# InkTime.net
KiCad netlist of a schematic drawn in EAGLE
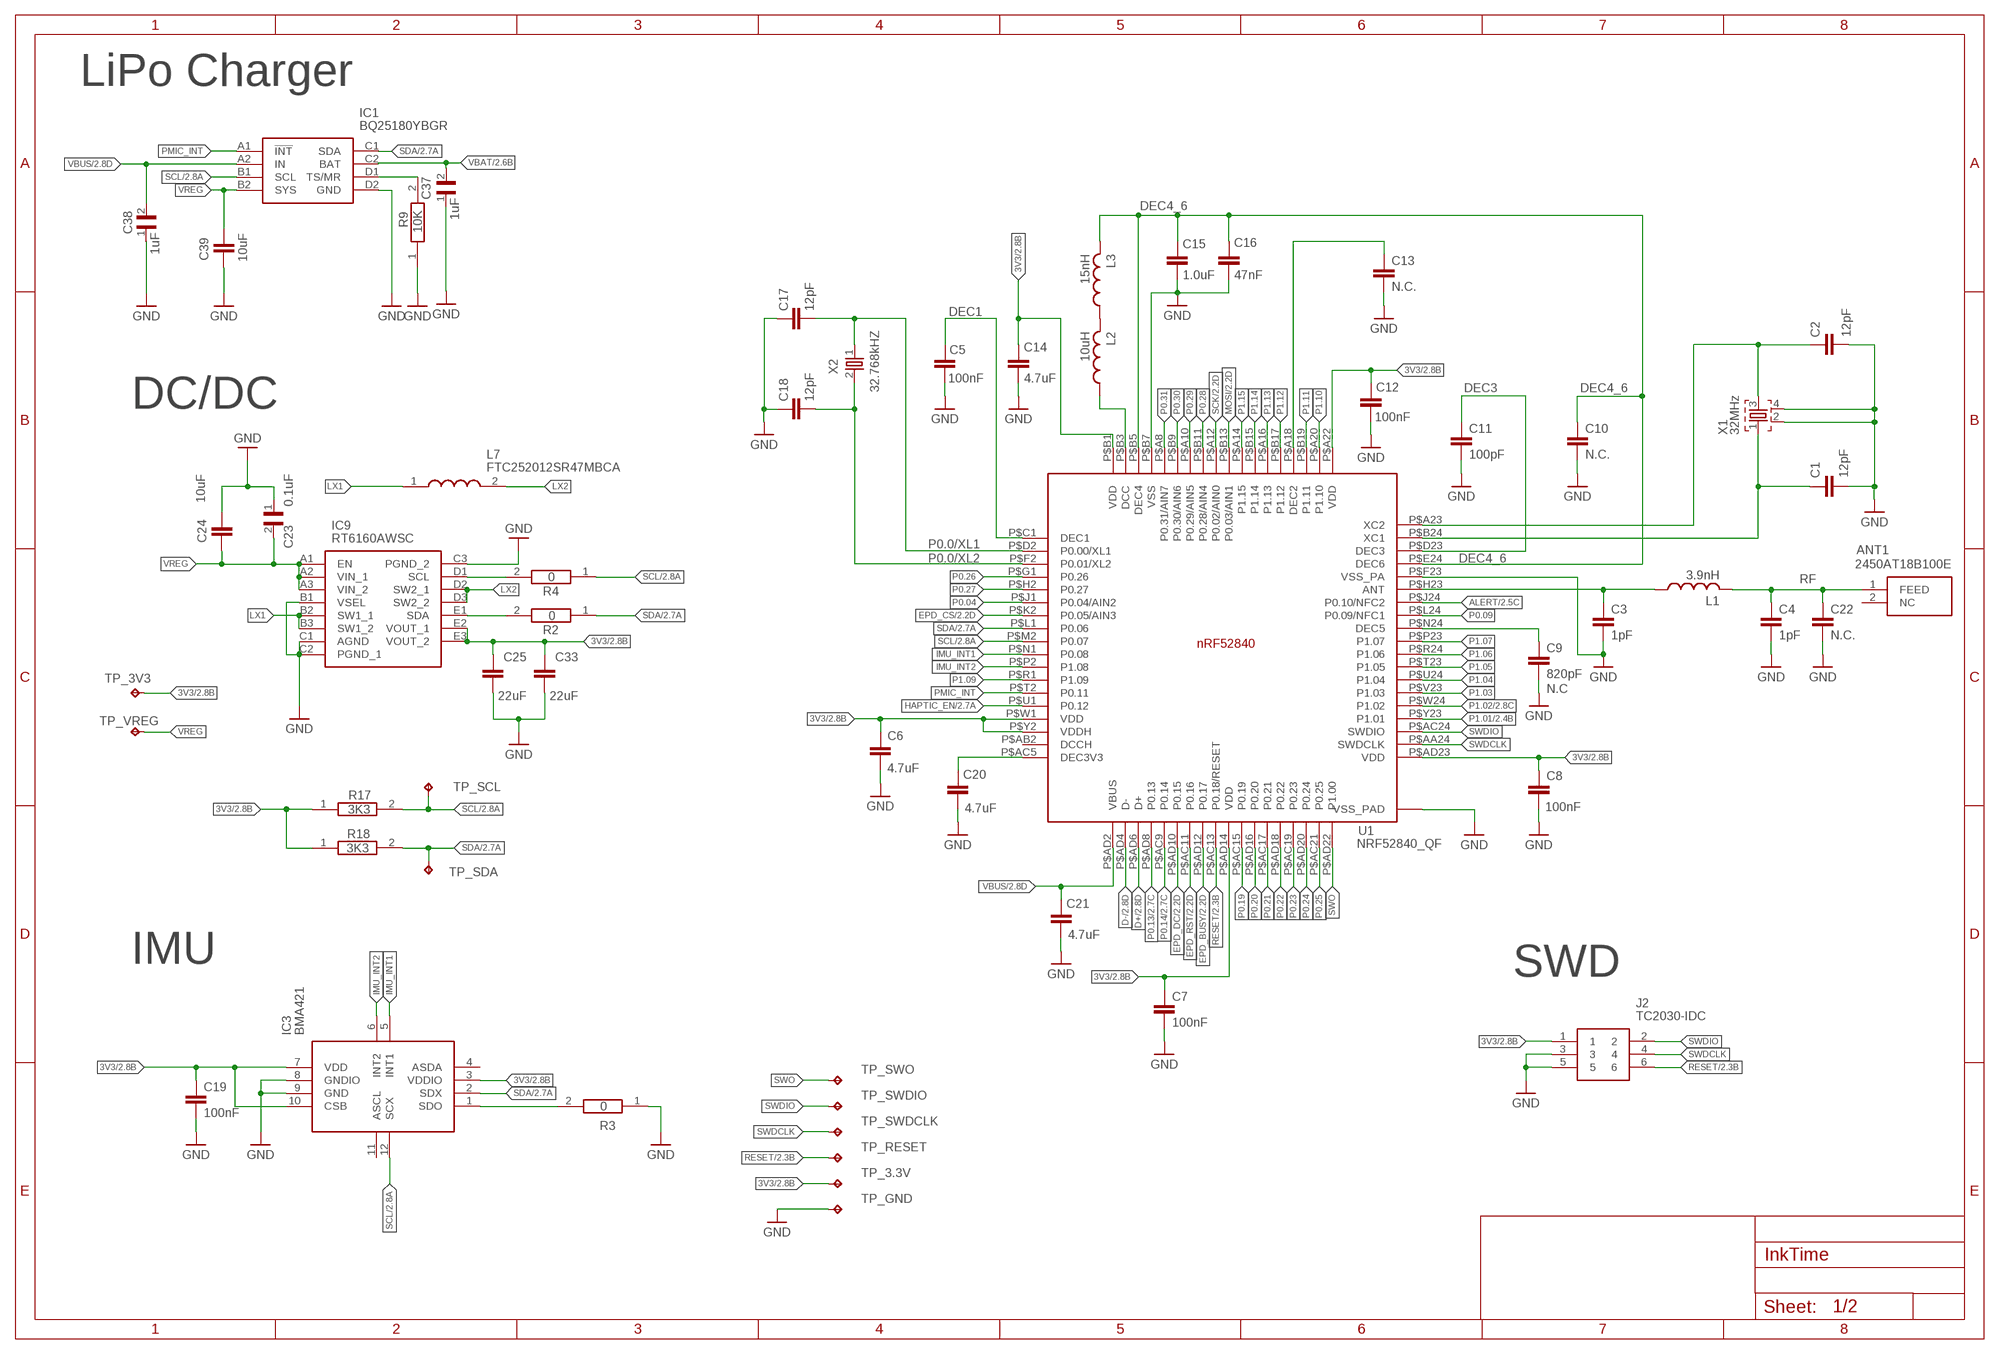
[diagram p0: schematic, sheet 1]
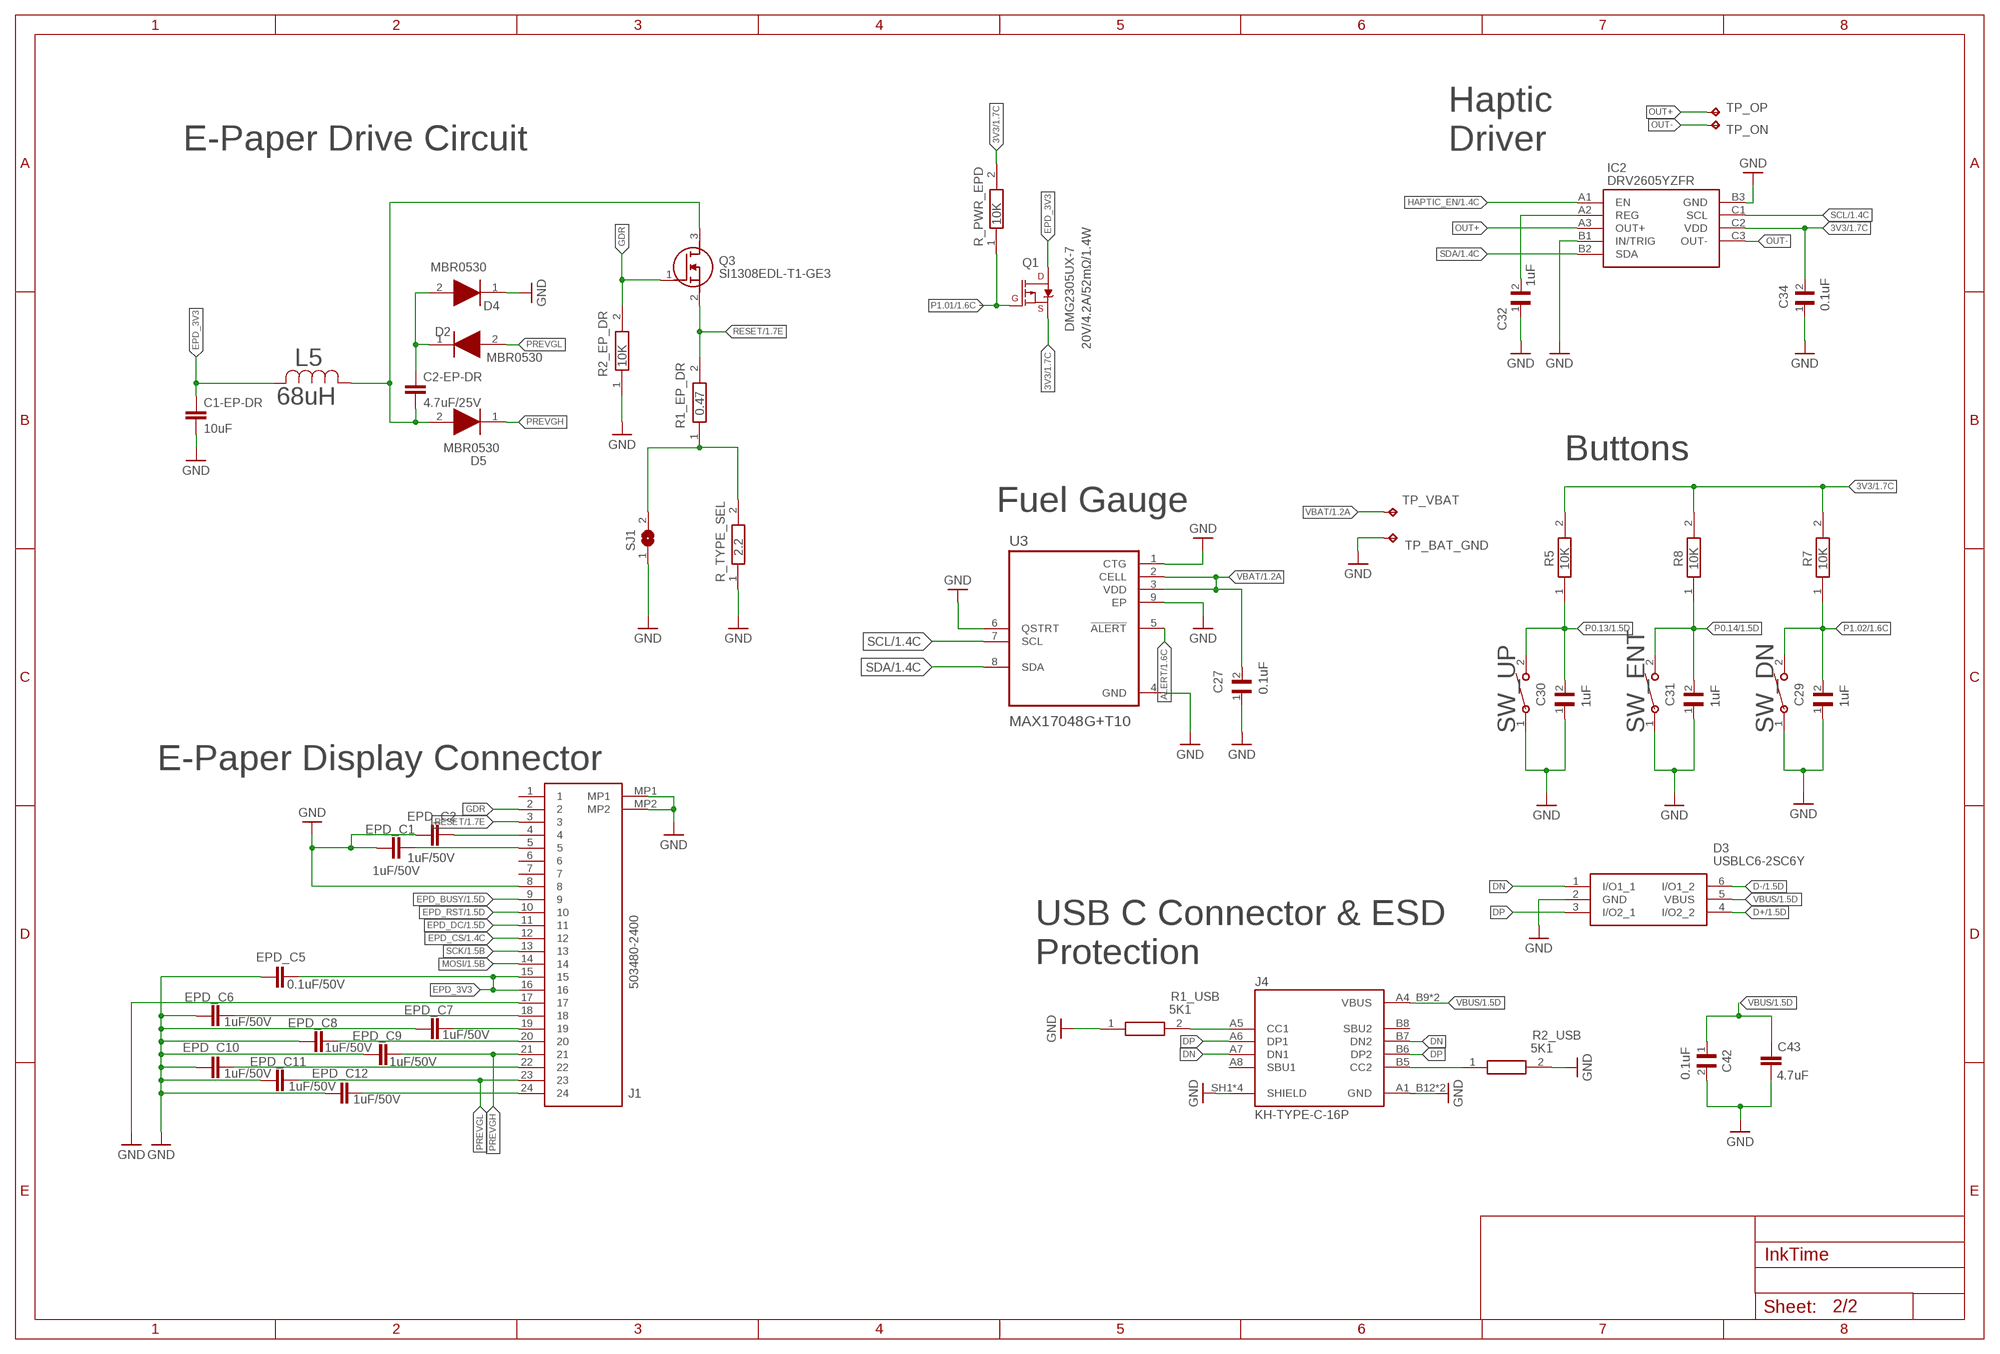
[diagram p1: schematic, sheet 2]

(export (version "E")
  (design (tool "Eeschema 10.0.6"))
  (components
    (comp (ref "ANT1")
      (value "2450AT18B100E")
      (footprint "eagle-import:2450AT18B100E_ANTC3216X140N")
      (fields (field (name "MOUSER_PART_NUMBER") "609-2450AT18B100E"))
      (libsource (lib "eagle-import") (part "2450AT18B100E_2450AT18B100E"))
    )
    (comp (ref "C1")
      (value "12pF")
      (footprint "eagle-import:NORDIC_NRF_3_RESC0201_L")
      (libsource (lib "eagle-import") (part "NORDIC_NRF_3_CAPACITOR_0201_L"))
    )
    (comp (ref "C2")
      (value "12pF")
      (footprint "eagle-import:NORDIC_NRF_3_RESC0201_L")
      (libsource (lib "eagle-import") (part "NORDIC_NRF_3_CAPACITOR_0201_L"))
    )
    (comp (ref "C3")
      (value "1pF")
      (footprint "eagle-import:NORDIC_NRF_3_RESC0201_L")
      (libsource (lib "eagle-import") (part "NORDIC_NRF_3_CAPACITOR_0201_L"))
    )
    (comp (ref "C4")
      (value "1pF")
      (footprint "eagle-import:NORDIC_NRF_3_RESC0201_L")
      (libsource (lib "eagle-import") (part "NORDIC_NRF_3_CAPACITOR_0201_L"))
    )
    (comp (ref "C5")
      (value "100nF")
      (footprint "eagle-import:PERFECT_0402_0402")
      (libsource (lib "eagle-import") (part "PERFECT_0402_CAP_0402"))
    )
    (comp (ref "C6")
      (value "4.7uF")
      (footprint "eagle-import:PERFECT_0402_0402")
      (libsource (lib "eagle-import") (part "PERFECT_0402_CAP_0402"))
    )
    (comp (ref "C7")
      (value "100nF")
      (footprint "eagle-import:NORDIC_NRF_3_RESC0201_L")
      (libsource (lib "eagle-import") (part "NORDIC_NRF_3_CAPACITOR_0201_L"))
    )
    (comp (ref "C8")
      (value "100nF")
      (footprint "eagle-import:NORDIC_NRF_3_RESC0201_L")
      (libsource (lib "eagle-import") (part "NORDIC_NRF_3_CAPACITOR_0201_L"))
    )
    (comp (ref "C9")
      (value "820pF")
      (footprint "eagle-import:NORDIC_NRF_3_RESC0201_L")
      (libsource (lib "eagle-import") (part "NORDIC_NRF_3_CAPACITOR_0201_L"))
    )
    (comp (ref "C10")
      (value "N.C.")
      (footprint "eagle-import:NORDIC_NRF_3_RESC0201_L")
      (libsource (lib "eagle-import") (part "NORDIC_NRF_3_CAPACITOR_0201_L"))
    )
    (comp (ref "C11")
      (value "100pF")
      (footprint "eagle-import:NORDIC_NRF_3_RESC0201_L")
      (libsource (lib "eagle-import") (part "NORDIC_NRF_3_CAPACITOR_0201_L"))
    )
    (comp (ref "C12")
      (value "100nF")
      (footprint "eagle-import:NORDIC_NRF_3_RESC0201_L")
      (libsource (lib "eagle-import") (part "NORDIC_NRF_3_CAPACITOR_0201_L"))
    )
    (comp (ref "C13")
      (value "N.C.")
      (footprint "eagle-import:NORDIC_NRF_3_RESC0201_L")
      (libsource (lib "eagle-import") (part "NORDIC_NRF_3_CAPACITOR_0201_L"))
    )
    (comp (ref "C14")
      (value "4.7uF")
      (footprint "eagle-import:PERFECT_0402_0402")
      (libsource (lib "eagle-import") (part "PERFECT_0402_CAP_0402"))
    )
    (comp (ref "C15")
      (value "1.0uF")
      (footprint "eagle-import:PERFECT_0402_0402")
      (libsource (lib "eagle-import") (part "PERFECT_0402_CAP_0402"))
    )
    (comp (ref "C16")
      (value "47nF")
      (footprint "eagle-import:NORDIC_NRF_3_RESC0201_L")
      (libsource (lib "eagle-import") (part "NORDIC_NRF_3_CAPACITOR_0201_L"))
    )
    (comp (ref "C17")
      (value "12pF")
      (footprint "eagle-import:NORDIC_NRF_3_RESC0201_L")
      (libsource (lib "eagle-import") (part "NORDIC_NRF_3_CAPACITOR_0201_L"))
    )
    (comp (ref "C18")
      (value "12pF")
      (footprint "eagle-import:NORDIC_NRF_3_RESC0201_L")
      (libsource (lib "eagle-import") (part "NORDIC_NRF_3_CAPACITOR_0201_L"))
    )
    (comp (ref "C19")
      (value "100nF")
      (footprint "eagle-import:NORDIC_NRF_3_RESC0201_L")
      (libsource (lib "eagle-import") (part "NORDIC_NRF_3_CAPACITOR_0201_L"))
    )
    (comp (ref "C20")
      (value "4.7uF")
      (footprint "eagle-import:PERFECT_0402_0402")
      (libsource (lib "eagle-import") (part "PERFECT_0402_CAP_0402"))
    )
    (comp (ref "C21")
      (value "4.7uF")
      (footprint "eagle-import:PERFECT_0402_0402")
      (libsource (lib "eagle-import") (part "PERFECT_0402_CAP_0402"))
    )
    (comp (ref "C22")
      (value "N.C.")
      (footprint "eagle-import:NORDIC_NRF_3_RESC0201_L")
      (libsource (lib "eagle-import") (part "NORDIC_NRF_3_CAPACITOR_0201_L"))
    )
    (comp (ref "C23")
      (value "0.1uF")
      (footprint "eagle-import:GRM011R60J152KE01L_1_0201")
      (libsource (lib "eagle-import") (part "GRM011R60J152KE01L_1_GRM011R60J152KE01L"))
    )
    (comp (ref "C24")
      (value "10uF")
      (footprint "eagle-import:PERFECT_0402_0402")
      (libsource (lib "eagle-import") (part "PERFECT_0402_CAP_0402"))
    )
    (comp (ref "C25")
      (value "22uF")
      (footprint "eagle-import:PERFECT_0402_0402")
      (libsource (lib "eagle-import") (part "PERFECT_0402_CAP_0402"))
    )
    (comp (ref "C33")
      (value "22uF")
      (footprint "eagle-import:PERFECT_0402_0402")
      (libsource (lib "eagle-import") (part "PERFECT_0402_CAP_0402"))
    )
    (comp (ref "C37")
      (value "1uF")
      (footprint "eagle-import:GRM011R60J152KE01L_1_0201")
      (libsource (lib "eagle-import") (part "GRM011R60J152KE01L_1_GRM011R60J152KE01L"))
    )
    (comp (ref "C38")
      (value "1uF")
      (footprint "eagle-import:GRM011R60J152KE01L_1_0201")
      (libsource (lib "eagle-import") (part "GRM011R60J152KE01L_1_GRM011R60J152KE01L"))
    )
    (comp (ref "C39")
      (value "10uF")
      (footprint "eagle-import:PERFECT_0402_0402")
      (libsource (lib "eagle-import") (part "PERFECT_0402_CAP_0402"))
    )
    (comp (ref "IC1")
      (value "BQ25180YBGR")
      (footprint "eagle-import:BQ25180YBGR_BGA8C40P2X4_100X155X50")
      (fields (field (name "MOUSER_PART_NUMBER") "595-BQ25180YBGR"))
      (libsource (lib "eagle-import") (part "BQ25180YBGR_BQ25180YBGR"))
    )
    (comp (ref "IC3")
      (value "BMA421")
      (footprint "eagle-import:BMA423_BMA423")
      (fields (field (name "ARROW_PART_NUMBER") "BMA423") (field (name "MOUSER_PART_NUMBER") "262-BMA423"))
      (libsource (lib "eagle-import") (part "BMA423_BMA423"))
    )
    (comp (ref "IC9")
      (value "RT6160AWSC")
      (footprint "eagle-import:RT6160AWSC_BGA15C40P3X5_140X230X60")
      (fields (field (name "MOUSER_PART_NUMBER") "835-RT6160AWSC"))
      (libsource (lib "eagle-import") (part "RT6160AWSC_RT6160AWSC"))
    )
    (comp (ref "J2")
      (value "TC2030-IDC")
      (footprint "eagle-import:TC2030-IDC_TC2030IDC")
      (libsource (lib "eagle-import") (part "TC2030-IDC_TC2030-IDC"))
    )
    (comp (ref "L1")
      (value "3.9nH")
      (footprint "eagle-import:NORDIC_NRF_2_RESC0402_L")
      (libsource (lib "eagle-import") (part "NORDIC_NRF_2_INDUCTOR_0402_L"))
    )
    (comp (ref "L2")
      (value "10uH")
      (footprint "eagle-import:NORDIC_NRF_2_RESC0402_L")
      (libsource (lib "eagle-import") (part "NORDIC_NRF_2_INDUCTOR_0402_L"))
    )
    (comp (ref "L3")
      (value "15nH")
      (footprint "eagle-import:NORDIC_NRF_2_RESC0402_L")
      (libsource (lib "eagle-import") (part "NORDIC_NRF_2_INDUCTOR_0402_L"))
    )
    (comp (ref "L7")
      (value "FTC252012SR47MBCA")
      (footprint "eagle-import:MLP2016SR47MT0S1_INDC2016X100N")
      (libsource (lib "eagle-import") (part "MLP2016SR47MT0S1_FTC252012SR47MBCA"))
    )
    (comp (ref "R2")
      (value "0")
      (footprint "eagle-import:ERA-1AEB3401C_0201")
      (libsource (lib "eagle-import") (part "ERA-1AEB3401C_CPF0201D7K68C1"))
    )
    (comp (ref "R3")
      (value "0")
      (footprint "eagle-import:ERA-1AEB3401C_0201")
      (libsource (lib "eagle-import") (part "ERA-1AEB3401C_CPF0201D7K68C1"))
    )
    (comp (ref "R4")
      (value "0")
      (footprint "eagle-import:ERA-1AEB3401C_0201")
      (libsource (lib "eagle-import") (part "ERA-1AEB3401C_CPF0201D7K68C1"))
    )
    (comp (ref "R9")
      (value "10K")
      (footprint "eagle-import:ERA-1AEB3401C_0201")
      (libsource (lib "eagle-import") (part "ERA-1AEB3401C_CPF0201D7K68C1"))
    )
    (comp (ref "R17")
      (value "3K3")
      (footprint "eagle-import:ERA-1AEB3401C_0201")
      (libsource (lib "eagle-import") (part "ERA-1AEB3401C_CPF0201D7K68C1"))
    )
    (comp (ref "R18")
      (value "3K3")
      (footprint "eagle-import:ERA-1AEB3401C_0201")
      (libsource (lib "eagle-import") (part "ERA-1AEB3401C_CPF0201D7K68C1"))
    )
    (comp (ref "TP_3.3V")
      (value "HECTOR_WATCH_1_TPTP20R")
      (footprint "eagle-import:HECTOR_WATCH_1_TP20R")
      (libsource (lib "eagle-import") (part "HECTOR_WATCH_1_TPTP20R"))
    )
    (comp (ref "TP_3V3")
      (value "HECTOR_WATCH_1_TPTP20R")
      (footprint "eagle-import:HECTOR_WATCH_1_TP20R")
      (libsource (lib "eagle-import") (part "HECTOR_WATCH_1_TPTP20R"))
    )
    (comp (ref "TP_GND")
      (value "HECTOR_WATCH_1_TPTP20R")
      (footprint "eagle-import:HECTOR_WATCH_1_TP20R")
      (libsource (lib "eagle-import") (part "HECTOR_WATCH_1_TPTP20R"))
    )
    (comp (ref "TP_RESET")
      (value "HECTOR_WATCH_1_TPTP20R")
      (footprint "eagle-import:HECTOR_WATCH_1_TP20R")
      (libsource (lib "eagle-import") (part "HECTOR_WATCH_1_TPTP20R"))
    )
    (comp (ref "TP_SCL")
      (value "HECTOR_WATCH_1_TPTP20R")
      (footprint "eagle-import:HECTOR_WATCH_1_TP20R")
      (libsource (lib "eagle-import") (part "HECTOR_WATCH_1_TPTP20R"))
    )
    (comp (ref "TP_SDA")
      (value "HECTOR_WATCH_1_TPTP20R")
      (footprint "eagle-import:HECTOR_WATCH_1_TP20R")
      (libsource (lib "eagle-import") (part "HECTOR_WATCH_1_TPTP20R"))
    )
    (comp (ref "TP_SWDCLK")
      (value "HECTOR_WATCH_1_TPTP20R")
      (footprint "eagle-import:HECTOR_WATCH_1_TP20R")
      (libsource (lib "eagle-import") (part "HECTOR_WATCH_1_TPTP20R"))
    )
    (comp (ref "TP_SWDIO")
      (value "HECTOR_WATCH_1_TPTP20R")
      (footprint "eagle-import:HECTOR_WATCH_1_TP20R")
      (libsource (lib "eagle-import") (part "HECTOR_WATCH_1_TPTP20R"))
    )
    (comp (ref "TP_SWO")
      (value "HECTOR_WATCH_1_TPTP20R")
      (footprint "eagle-import:HECTOR_WATCH_1_TP20R")
      (libsource (lib "eagle-import") (part "HECTOR_WATCH_1_TPTP20R"))
    )
    (comp (ref "TP_VREG")
      (value "HECTOR_WATCH_1_TPTP20R")
      (footprint "eagle-import:HECTOR_WATCH_1_TP20R")
      (libsource (lib "eagle-import") (part "HECTOR_WATCH_1_TPTP20R"))
    )
    (comp (ref "U1")
      (value "NRF52840_QF")
      (footprint "eagle-import:NORDIC_NRF_4_AQFN50P700X700X85_HS-74N")
      (libsource (lib "eagle-import") (part "NORDIC_NRF_4_NRF52840_QF"))
    )
    (comp (ref "X1")
      (value "32MHz")
      (footprint "eagle-import:NORDIC_NRF_BT-XTAL_2016_N")
      (libsource (lib "eagle-import") (part "NORDIC_NRF_XTAL_32MHZ"))
    )
    (comp (ref "X2")
      (value "32.768kHZ")
      (footprint "eagle-import:NORDIC_NRF_1_XTAL_3215_N")
      (libsource (lib "eagle-import") (part "NORDIC_NRF_1_XTAL_32KHZ"))
    )
    (comp (ref "C1-EP-DR")
      (value "10uF")
      (footprint "eagle-import:PERFECT_0402_0402")
      (libsource (lib "eagle-import") (part "PERFECT_0402_CAP_0402"))
    )
    (comp (ref "C2-EP-DR")
      (value "4.7uF/25V")
      (footprint "eagle-import:PERFECT_0402_0402")
      (libsource (lib "eagle-import") (part "PERFECT_0402_CAP_0402"))
    )
    (comp (ref "C27")
      (value "0.1uF")
      (footprint "eagle-import:GRM011R60J152KE01L_1_0201")
      (libsource (lib "eagle-import") (part "GRM011R60J152KE01L_1_GRM011R60J152KE01L"))
    )
    (comp (ref "C29")
      (value "1uF")
      (footprint "eagle-import:GRM011R60J152KE01L_1_0201")
      (libsource (lib "eagle-import") (part "GRM011R60J152KE01L_1_GRM011R60J152KE01L"))
    )
    (comp (ref "C30")
      (value "1uF")
      (footprint "eagle-import:GRM011R60J152KE01L_1_0201")
      (libsource (lib "eagle-import") (part "GRM011R60J152KE01L_1_GRM011R60J152KE01L"))
    )
    (comp (ref "C31")
      (value "1uF")
      (footprint "eagle-import:GRM011R60J152KE01L_1_0201")
      (libsource (lib "eagle-import") (part "GRM011R60J152KE01L_1_GRM011R60J152KE01L"))
    )
    (comp (ref "C32")
      (value "1uF")
      (footprint "eagle-import:GRM011R60J152KE01L_1_0201")
      (libsource (lib "eagle-import") (part "GRM011R60J152KE01L_1_GRM011R60J152KE01L"))
    )
    (comp (ref "C34")
      (value "0.1uF")
      (footprint "eagle-import:GRM011R60J152KE01L_1_0201")
      (libsource (lib "eagle-import") (part "GRM011R60J152KE01L_1_GRM011R60J152KE01L"))
    )
    (comp (ref "C42")
      (value "0.1uF")
      (footprint "eagle-import:GRM011R60J152KE01L_1_0201")
      (libsource (lib "eagle-import") (part "GRM011R60J152KE01L_1_GRM011R60J152KE01L"))
    )
    (comp (ref "C43")
      (value "4.7uF")
      (footprint "eagle-import:PERFECT_0402_0402")
      (libsource (lib "eagle-import") (part "PERFECT_0402_CAP_0402"))
    )
    (comp (ref "D2")
      (value "MBR0530")
      (footprint "eagle-import:ESP32_C6_LIBRARY_5_SOD3716X135N")
      (fields (field (name "MF") "ON Semiconductor"))
      (libsource (lib "eagle-import") (part "ESP32_C6_LIBRARY_5_MBR0530"))
    )
    (comp (ref "D3")
      (value "USBLC6-2SC6Y")
      (footprint "eagle-import:ESP32_C6_LIBRARY_3_SOT95P280X145-6N")
      (fields (field (name "MF") "STMicroelectronics"))
      (libsource (lib "eagle-import") (part "ESP32_C6_LIBRARY_3_USBLC6-2SC6Y"))
    )
    (comp (ref "D4")
      (value "MBR0530")
      (footprint "eagle-import:ESP32_C6_LIBRARY_5_SOD3716X135N")
      (fields (field (name "MF") "ON Semiconductor"))
      (libsource (lib "eagle-import") (part "ESP32_C6_LIBRARY_5_MBR0530"))
    )
    (comp (ref "D5")
      (value "MBR0530")
      (footprint "eagle-import:ESP32_C6_LIBRARY_5_SOD3716X135N")
      (fields (field (name "MF") "ON Semiconductor"))
      (libsource (lib "eagle-import") (part "ESP32_C6_LIBRARY_5_MBR0530"))
    )
    (comp (ref "EPD_C1")
      (value "1uF/50V")
      (footprint "eagle-import:PERFECT_0402_0402")
      (libsource (lib "eagle-import") (part "PERFECT_0402_CAP_0402"))
    )
    (comp (ref "EPD_C2")
      (value "1uF/50V")
      (footprint "eagle-import:PERFECT_0402_0402")
      (libsource (lib "eagle-import") (part "PERFECT_0402_CAP_0402"))
    )
    (comp (ref "EPD_C5")
      (value "0.1uF/50V")
      (footprint "eagle-import:NORDIC_NRF_3_RESC0201_L")
      (libsource (lib "eagle-import") (part "NORDIC_NRF_3_CAPACITOR_0201_L"))
    )
    (comp (ref "EPD_C6")
      (value "1uF/50V")
      (footprint "eagle-import:PERFECT_0402_0402")
      (libsource (lib "eagle-import") (part "PERFECT_0402_CAP_0402"))
    )
    (comp (ref "EPD_C7")
      (value "1uF/50V")
      (footprint "eagle-import:PERFECT_0402_0402")
      (libsource (lib "eagle-import") (part "PERFECT_0402_CAP_0402"))
    )
    (comp (ref "EPD_C8")
      (value "1uF/50V")
      (footprint "eagle-import:PERFECT_0402_0402")
      (libsource (lib "eagle-import") (part "PERFECT_0402_CAP_0402"))
    )
    (comp (ref "EPD_C9")
      (value "1uF/50V")
      (footprint "eagle-import:PERFECT_0402_0402")
      (libsource (lib "eagle-import") (part "PERFECT_0402_CAP_0402"))
    )
    (comp (ref "EPD_C10")
      (value "1uF/50V")
      (footprint "eagle-import:PERFECT_0402_0402")
      (libsource (lib "eagle-import") (part "PERFECT_0402_CAP_0402"))
    )
    (comp (ref "EPD_C11")
      (value "1uF/50V")
      (footprint "eagle-import:PERFECT_0402_0402")
      (libsource (lib "eagle-import") (part "PERFECT_0402_CAP_0402"))
    )
    (comp (ref "EPD_C12")
      (value "1uF/50V")
      (footprint "eagle-import:PERFECT_0402_0402")
      (libsource (lib "eagle-import") (part "PERFECT_0402_CAP_0402"))
    )
    (comp (ref "IC2")
      (value "DRV2605YZFR")
      (footprint "eagle-import:DRV2605YZFR_BGA9C50P3X3_144X144X62")
      (libsource (lib "eagle-import") (part "DRV2605YZFR_DRV2605YZFR"))
    )
    (comp (ref "J1")
      (value "503480-2400")
      (footprint "eagle-import:503480-2400_5034802400")
      (fields (field (name "MOUSER_PART_NUMBER") "538-503480-2400"))
      (libsource (lib "eagle-import") (part "503480-2400_503480-2400"))
    )
    (comp (ref "J4")
      (value "KH-TYPE-C-16P")
      (footprint "eagle-import:KH-TYPE-C-16P_KINGHELM_KH-TYPE-C-16P")
      (fields (field (name "MF") "kinghelm"))
      (libsource (lib "eagle-import") (part "KH-TYPE-C-16P_KH-TYPE-C-16P"))
    )
    (comp (ref "L5")
      (value "68uH")
      (footprint "eagle-import:ESP32_C6_LIBRARY_2_IND_4828-WE-TPC_WRE")
      (fields
        (field (name "MANUFACTURER_PART_NUMBER") "744043680")
        (field (name "COPYRIGHT") "Copyright (C) 2024 Ultra Librarian. All rights reserved.")
      )
      (libsource (lib "eagle-import") (part "ESP32_C6_LIBRARY_2_744043680IND_4828-WE-TPC_WRE"))
    )
    (comp (ref "Q1")
      (value "20V/4.2A/52mΩ/1.4W")
      (footprint "eagle-import:ESP32_C6_LIBRARY_4_ESP32_C6_LIBRARY_4_ESP32_C6_LIBRARY_4_ESP32_C6_LIBRARY_4_ESP32_WROVER_SPARKFUN-DISCRETESEMI_SOT23-3")
      (libsource (lib "eagle-import") (part "ESP32_C6_LIBRARY_4_ESP32_WROVER_SPARKFUN-DISCRETESEMI_MOSFET_PCH-DMG2305UX-7"))
    )
    (comp (ref "Q3")
      (value "SI1308EDL-T1-GE3")
      (footprint "eagle-import:ESP32_C6_LIBRARY_6_SOT65P210X110-3N")
      (fields (field (name "MF") "Vishay Siliconix"))
      (libsource (lib "eagle-import") (part "ESP32_C6_LIBRARY_6_SI1308EDL-T1-GE3"))
    )
    (comp (ref "R1_EP_DR")
      (value "0.47")
      (footprint "eagle-import:ERA-1AEB3401C_0201")
      (libsource (lib "eagle-import") (part "ERA-1AEB3401C_CPF0201D7K68C1"))
    )
    (comp (ref "R1_USB")
      (value "5K1")
      (footprint "eagle-import:ERA-1AEB3401C_0201")
      (libsource (lib "eagle-import") (part "ERA-1AEB3401C_CPF0201D7K68C1"))
    )
    (comp (ref "R2_EP_DR")
      (value "10K")
      (footprint "eagle-import:ERA-1AEB3401C_0201")
      (libsource (lib "eagle-import") (part "ERA-1AEB3401C_CPF0201D7K68C1"))
    )
    (comp (ref "R2_USB")
      (value "5K1")
      (footprint "eagle-import:ERA-1AEB3401C_0201")
      (libsource (lib "eagle-import") (part "ERA-1AEB3401C_CPF0201D7K68C1"))
    )
    (comp (ref "R5")
      (value "10K")
      (footprint "eagle-import:ERA-1AEB3401C_0201")
      (libsource (lib "eagle-import") (part "ERA-1AEB3401C_CPF0201D7K68C1"))
    )
    (comp (ref "R7")
      (value "10K")
      (footprint "eagle-import:ERA-1AEB3401C_0201")
      (libsource (lib "eagle-import") (part "ERA-1AEB3401C_CPF0201D7K68C1"))
    )
    (comp (ref "R8")
      (value "10K")
      (footprint "eagle-import:ERA-1AEB3401C_0201")
      (libsource (lib "eagle-import") (part "ERA-1AEB3401C_CPF0201D7K68C1"))
    )
    (comp (ref "R_PWR_EPD")
      (value "10K")
      (footprint "eagle-import:ERA-1AEB3401C_0201")
      (libsource (lib "eagle-import") (part "ERA-1AEB3401C_CPF0201D7K68C1"))
    )
    (comp (ref "R_TYPE_SEL")
      (value "2.2")
      (footprint "eagle-import:ERA-1AEB3401C_0201")
      (libsource (lib "eagle-import") (part "ERA-1AEB3401C_CPF0201D7K68C1"))
    )
    (comp (ref "SJ1")
      (value "ESP32_C6_LIBRARY_7_JUMPER_SJ")
      (footprint "eagle-import:ESP32_C6_LIBRARY_7_JUMPER_SJ")
      (libsource (lib "eagle-import") (part "ESP32_C6_LIBRARY_7_JUMPER_SJ"))
    )
    (comp (ref "SW_DN")
      (value "2025-10-22_07-23-44_LIBRARY_EVP-AKE31ASW_EVP-AKE31A_PAN")
      (footprint "eagle-import:2025-10-22_07-23-44_LIBRARY_SW_EVP-AKE31A_PAN")
      (fields
        (field (name "MANUFACTURER_PART_NUMBER") "EVP-AKE31A")
        (field (name "COPYRIGHT") "Copyright (C) 2025 Ultra Librarian. All rights reserved.")
      )
      (libsource (lib "eagle-import") (part "2025-10-22_07-23-44_LIBRARY_EVP-AKE31ASW_EVP-AKE31A_PAN"))
    )
    (comp (ref "SW_ENT")
      (value "2025-10-22_07-23-44_LIBRARY_EVP-AKE31ASW_EVP-AKE31A_PAN")
      (footprint "eagle-import:2025-10-22_07-23-44_LIBRARY_SW_EVP-AKE31A_PAN")
      (fields
        (field (name "MANUFACTURER_PART_NUMBER") "EVP-AKE31A")
        (field (name "COPYRIGHT") "Copyright (C) 2025 Ultra Librarian. All rights reserved.")
      )
      (libsource (lib "eagle-import") (part "2025-10-22_07-23-44_LIBRARY_EVP-AKE31ASW_EVP-AKE31A_PAN"))
    )
    (comp (ref "SW_UP")
      (value "2025-10-22_07-23-44_LIBRARY_EVP-AKE31ASW_EVP-AKE31A_PAN")
      (footprint "eagle-import:2025-10-22_07-23-44_LIBRARY_SW_EVP-AKE31A_PAN")
      (fields
        (field (name "MANUFACTURER_PART_NUMBER") "EVP-AKE31A")
        (field (name "COPYRIGHT") "Copyright (C) 2025 Ultra Librarian. All rights reserved.")
      )
      (libsource (lib "eagle-import") (part "2025-10-22_07-23-44_LIBRARY_EVP-AKE31ASW_EVP-AKE31A_PAN"))
    )
    (comp (ref "TP_BAT_GND")
      (value "HECTOR_WATCH_1_TPTP20R")
      (footprint "eagle-import:HECTOR_WATCH_1_TP20R")
      (libsource (lib "eagle-import") (part "HECTOR_WATCH_1_TPTP20R"))
    )
    (comp (ref "TP_ON")
      (value "HECTOR_WATCH_1_TPTP20R")
      (footprint "eagle-import:HECTOR_WATCH_1_TP20R")
      (libsource (lib "eagle-import") (part "HECTOR_WATCH_1_TPTP20R"))
    )
    (comp (ref "TP_OP")
      (value "HECTOR_WATCH_1_TPTP20R")
      (footprint "eagle-import:HECTOR_WATCH_1_TP20R")
      (libsource (lib "eagle-import") (part "HECTOR_WATCH_1_TPTP20R"))
    )
    (comp (ref "TP_VBAT")
      (value "HECTOR_WATCH_1_TPTP20R")
      (footprint "eagle-import:HECTOR_WATCH_1_TP20R")
      (libsource (lib "eagle-import") (part "HECTOR_WATCH_1_TPTP20R"))
    )
    (comp (ref "U3")
      (value "MAX17048G+T10")
      (footprint "eagle-import:ESP32_C6_LIBRARY_SON50P200X200X80-9N")
      (fields (field (name "MF") "Analog Devices"))
      (libsource (lib "eagle-import") (part "ESP32_C6_LIBRARY_MAX17048G+T10"))
    )
  )
  (nets
    (net (code "1") (name "3V3") (class "Default")
      (node (ref "C12") (pin "1") (pinfunction "1_1") (pintype "passive"))
      (node (ref "C14") (pin "1") (pinfunction "1_1") (pintype "passive"))
      (node (ref "C19") (pin "1") (pinfunction "1_1") (pintype "passive"))
      (node (ref "C25") (pin "1") (pinfunction "1_1") (pintype "passive"))
      (node (ref "C33") (pin "1") (pinfunction "1_1") (pintype "passive"))
      (node (ref "C34") (pin "2") (pinfunction "2_2") (pintype "passive"))
      (node (ref "C6") (pin "1") (pinfunction "1_1") (pintype "passive"))
      (node (ref "C7") (pin "1") (pinfunction "1_1") (pintype "passive"))
      (node (ref "C8") (pin "1") (pinfunction "1_1") (pintype "passive"))
      (node (ref "IC2") (pin "C2") (pinfunction "VDD_C2") (pintype "bidirectional"))
      (node (ref "IC3") (pin "10") (pinfunction "CSB_10") (pintype "bidirectional"))
      (node (ref "IC3") (pin "3") (pinfunction "VDDIO_3") (pintype "bidirectional"))
      (node (ref "IC3") (pin "7") (pinfunction "VDD_7") (pintype "bidirectional"))
      (node (ref "IC9") (pin "E2") (pinfunction "VOUT_1_E2") (pintype "bidirectional"))
      (node (ref "IC9") (pin "E3") (pinfunction "VOUT_2_E3") (pintype "bidirectional"))
      (node (ref "J2") (pin "1") (pinfunction "1_1") (pintype "bidirectional"))
      (node (ref "Q1") (pin "2") (pinfunction "S_2") (pintype "bidirectional"))
      (node (ref "R17") (pin "1") (pinfunction "1_1") (pintype "bidirectional"))
      (node (ref "R18") (pin "1") (pinfunction "1_1") (pintype "bidirectional"))
      (node (ref "R5") (pin "2") (pinfunction "2_2") (pintype "bidirectional"))
      (node (ref "R7") (pin "2") (pinfunction "2_2") (pintype "bidirectional"))
      (node (ref "R8") (pin "2") (pinfunction "2_2") (pintype "bidirectional"))
      (node (ref "R_PWR_EPD") (pin "2") (pinfunction "2_2") (pintype "bidirectional"))
      (node (ref "TP_3.3V") (pin "TP") (pinfunction "TP_TP") (pintype "input"))
      (node (ref "TP_3V3") (pin "TP") (pinfunction "TP_TP") (pintype "input"))
      (node (ref "U1") (pin "P$A22") (pinfunction "VDD_P$A22") (pintype "power_in"))
      (node (ref "U1") (pin "P$AD14") (pinfunction "VDD_P$AD14") (pintype "power_in"))
      (node (ref "U1") (pin "P$AD23") (pinfunction "VDD_P$AD23") (pintype "power_in"))
      (node (ref "U1") (pin "P$B1") (pinfunction "VDD_P$B1") (pintype "power_in"))
      (node (ref "U1") (pin "P$W1") (pinfunction "VDD_P$W1") (pintype "power_in"))
      (node (ref "U1") (pin "P$Y2") (pinfunction "VDDH_P$Y2") (pintype "power_in"))
    )
    (net (code "2") (name "ALERT") (class "Default")
      (node (ref "U1") (pin "P$J24") (pinfunction "P0.10/NFC2_P$J24") (pintype "bidirectional"))
      (node (ref "U3") (pin "5") (pinfunction "~{ALERT}_5") (pintype "output"))
    )
    (net (code "3") (name "D+") (class "Default")
      (node (ref "D3") (pin "4") (pinfunction "I/O2_2_4") (pintype "bidirectional"))
      (node (ref "U1") (pin "P$AD6") (pinfunction "D+_P$AD6") (pintype "bidirectional"))
    )
    (net (code "4") (name "D-") (class "Default")
      (node (ref "D3") (pin "6") (pinfunction "I/O1_2_6") (pintype "bidirectional"))
      (node (ref "U1") (pin "P$AD4") (pinfunction "D-_P$AD4") (pintype "bidirectional"))
    )
    (net (code "5") (name "DEC1") (class "Default")
      (node (ref "C5") (pin "1") (pinfunction "1_1") (pintype "passive"))
      (node (ref "U1") (pin "P$C1") (pinfunction "DEC1_P$C1") (pintype "power_in"))
    )
    (net (code "6") (name "DEC3") (class "Default")
      (node (ref "C11") (pin "1") (pinfunction "1_1") (pintype "passive"))
      (node (ref "U1") (pin "P$D23") (pinfunction "DEC3_P$D23") (pintype "bidirectional"))
    )
    (net (code "7") (name "DEC4_6") (class "Default")
      (node (ref "C10") (pin "1") (pinfunction "1_1") (pintype "passive"))
      (node (ref "C15") (pin "1") (pinfunction "1_1") (pintype "passive"))
      (node (ref "C16") (pin "1") (pinfunction "1_1") (pintype "passive"))
      (node (ref "L3") (pin "2") (pinfunction "2_2") (pintype "passive"))
      (node (ref "U1") (pin "P$B5") (pinfunction "DEC4_P$B5") (pintype "power_in"))
      (node (ref "U1") (pin "P$E24") (pinfunction "DEC6_P$E24") (pintype "bidirectional"))
    )
    (net (code "8") (name "DN") (class "Default")
      (node (ref "D3") (pin "1") (pinfunction "I/O1_1_1") (pintype "bidirectional"))
      (node (ref "J4") (pin "A7") (pinfunction "DN1_A7") (pintype "bidirectional"))
      (node (ref "J4") (pin "B7") (pinfunction "DN2_B7") (pintype "bidirectional"))
    )
    (net (code "9") (name "DP") (class "Default")
      (node (ref "D3") (pin "3") (pinfunction "I/O2_1_3") (pintype "bidirectional"))
      (node (ref "J4") (pin "A6") (pinfunction "DP1_A6") (pintype "bidirectional"))
      (node (ref "J4") (pin "B6") (pinfunction "DP2_B6") (pintype "bidirectional"))
    )
    (net (code "10") (name "EPD_3V3") (class "Default")
      (node (ref "C1-EP-DR") (pin "1") (pinfunction "1_1") (pintype "passive"))
      (node (ref "EPD_C5") (pin "2") (pinfunction "2_2") (pintype "passive"))
      (node (ref "J1") (pin "15") (pinfunction "15_15") (pintype "bidirectional"))
      (node (ref "J1") (pin "16") (pinfunction "16_16") (pintype "bidirectional"))
      (node (ref "L5") (pin "2") (pinfunction "2_2") (pintype "passive"))
      (node (ref "Q1") (pin "3") (pinfunction "D_3") (pintype "bidirectional"))
    )
    (net (code "11") (name "EPD_BUSY") (class "Default")
      (node (ref "J1") (pin "9") (pinfunction "9_9") (pintype "bidirectional"))
      (node (ref "U1") (pin "P$AD12") (pinfunction "P0.17_P$AD12") (pintype "bidirectional"))
    )
    (net (code "12") (name "EPD_CS") (class "Default")
      (node (ref "J1") (pin "12") (pinfunction "12_12") (pintype "bidirectional"))
      (node (ref "U1") (pin "P$K2") (pinfunction "P0.05/AIN3_P$K2") (pintype "bidirectional"))
    )
    (net (code "13") (name "EPD_DC") (class "Default")
      (node (ref "J1") (pin "11") (pinfunction "11_11") (pintype "bidirectional"))
      (node (ref "U1") (pin "P$AD10") (pinfunction "P0.15_P$AD10") (pintype "bidirectional"))
    )
    (net (code "14") (name "EPD_RST") (class "Default")
      (node (ref "J1") (pin "10") (pinfunction "10_10") (pintype "bidirectional"))
      (node (ref "U1") (pin "P$AC11") (pinfunction "P0.16_P$AC11") (pintype "bidirectional"))
    )
    (net (code "15") (name "GDR") (class "Default")
      (node (ref "J1") (pin "2") (pinfunction "2_2") (pintype "bidirectional"))
      (node (ref "Q3") (pin "1") (pinfunction "G_1") (pintype "bidirectional"))
      (node (ref "R2_EP_DR") (pin "2") (pinfunction "2_2") (pintype "bidirectional"))
    )
    (net (code "16") (name "GND") (class "Default")
      (node (ref "C1") (pin "1") (pinfunction "1_1") (pintype "passive"))
      (node (ref "C1-EP-DR") (pin "2") (pinfunction "2_2") (pintype "passive"))
      (node (ref "C10") (pin "2") (pinfunction "2_2") (pintype "passive"))
      (node (ref "C11") (pin "2") (pinfunction "2_2") (pintype "passive"))
      (node (ref "C12") (pin "2") (pinfunction "2_2") (pintype "passive"))
      (node (ref "C13") (pin "2") (pinfunction "2_2") (pintype "passive"))
      (node (ref "C14") (pin "2") (pinfunction "2_2") (pintype "passive"))
      (node (ref "C15") (pin "2") (pinfunction "2_2") (pintype "passive"))
      (node (ref "C16") (pin "2") (pinfunction "2_2") (pintype "passive"))
      (node (ref "C17") (pin "1") (pinfunction "1_1") (pintype "passive"))
      (node (ref "C18") (pin "1") (pinfunction "1_1") (pintype "passive"))
      (node (ref "C19") (pin "2") (pinfunction "2_2") (pintype "passive"))
      (node (ref "C2") (pin "1") (pinfunction "1_1") (pintype "passive"))
      (node (ref "C20") (pin "2") (pinfunction "2_2") (pintype "passive"))
      (node (ref "C21") (pin "2") (pinfunction "2_2") (pintype "passive"))
      (node (ref "C22") (pin "2") (pinfunction "2_2") (pintype "passive"))
      (node (ref "C23") (pin "1") (pinfunction "1_1") (pintype "passive"))
      (node (ref "C24") (pin "1") (pinfunction "1_1") (pintype "passive"))
      (node (ref "C25") (pin "2") (pinfunction "2_2") (pintype "passive"))
      (node (ref "C27") (pin "1") (pinfunction "1_1") (pintype "passive"))
      (node (ref "C29") (pin "1") (pinfunction "1_1") (pintype "passive"))
      (node (ref "C3") (pin "2") (pinfunction "2_2") (pintype "passive"))
      (node (ref "C30") (pin "1") (pinfunction "1_1") (pintype "passive"))
      (node (ref "C31") (pin "1") (pinfunction "1_1") (pintype "passive"))
      (node (ref "C32") (pin "1") (pinfunction "1_1") (pintype "passive"))
      (node (ref "C33") (pin "2") (pinfunction "2_2") (pintype "passive"))
      (node (ref "C34") (pin "1") (pinfunction "1_1") (pintype "passive"))
      (node (ref "C37") (pin "1") (pinfunction "1_1") (pintype "passive"))
      (node (ref "C38") (pin "1") (pinfunction "1_1") (pintype "passive"))
      (node (ref "C39") (pin "2") (pinfunction "2_2") (pintype "passive"))
      (node (ref "C4") (pin "2") (pinfunction "2_2") (pintype "passive"))
      (node (ref "C42") (pin "2") (pinfunction "2_2") (pintype "passive"))
      (node (ref "C43") (pin "1") (pinfunction "1_1") (pintype "passive"))
      (node (ref "C5") (pin "2") (pinfunction "2_2") (pintype "passive"))
      (node (ref "C6") (pin "2") (pinfunction "2_2") (pintype "passive"))
      (node (ref "C7") (pin "2") (pinfunction "2_2") (pintype "passive"))
      (node (ref "C8") (pin "2") (pinfunction "2_2") (pintype "passive"))
      (node (ref "C9") (pin "2") (pinfunction "2_2") (pintype "passive"))
      (node (ref "D3") (pin "2") (pinfunction "GND_2") (pintype "bidirectional"))
      (node (ref "D4") (pin "1") (pinfunction "K_1") (pintype "bidirectional"))
      (node (ref "EPD_C1") (pin "1") (pinfunction "1_1") (pintype "passive"))
      (node (ref "EPD_C10") (pin "1") (pinfunction "1_1") (pintype "passive"))
      (node (ref "EPD_C11") (pin "1") (pinfunction "1_1") (pintype "passive"))
      (node (ref "EPD_C12") (pin "1") (pinfunction "1_1") (pintype "passive"))
      (node (ref "EPD_C2") (pin "1") (pinfunction "1_1") (pintype "passive"))
      (node (ref "EPD_C5") (pin "1") (pinfunction "1_1") (pintype "passive"))
      (node (ref "EPD_C6") (pin "1") (pinfunction "1_1") (pintype "passive"))
      (node (ref "EPD_C7") (pin "1") (pinfunction "1_1") (pintype "passive"))
      (node (ref "EPD_C8") (pin "1") (pinfunction "1_1") (pintype "passive"))
      (node (ref "EPD_C9") (pin "1") (pinfunction "1_1") (pintype "passive"))
      (node (ref "IC1") (pin "D2") (pinfunction "GND_D2") (pintype "bidirectional"))
      (node (ref "IC2") (pin "B1") (pinfunction "IN/TRIG_B1") (pintype "bidirectional"))
      (node (ref "IC2") (pin "B3") (pinfunction "GND_B3") (pintype "bidirectional"))
      (node (ref "IC3") (pin "8") (pinfunction "GNDIO_8") (pintype "bidirectional"))
      (node (ref "IC3") (pin "9") (pinfunction "GND_9") (pintype "bidirectional"))
      (node (ref "IC9") (pin "B1") (pinfunction "VSEL_B1") (pintype "bidirectional"))
      (node (ref "IC9") (pin "C1") (pinfunction "AGND_C1") (pintype "bidirectional"))
      (node (ref "IC9") (pin "C2") (pinfunction "PGND_1_C2") (pintype "bidirectional"))
      (node (ref "IC9") (pin "C3") (pinfunction "PGND_2_C3") (pintype "bidirectional"))
      (node (ref "J1") (pin "17") (pinfunction "17_17") (pintype "bidirectional"))
      (node (ref "J1") (pin "8") (pinfunction "8_8") (pintype "bidirectional"))
      (node (ref "J1") (pin "MP1") (pinfunction "MP1_MP1") (pintype "bidirectional"))
      (node (ref "J1") (pin "MP2") (pinfunction "MP2_MP2") (pintype "bidirectional"))
      (node (ref "J2") (pin "3") (pinfunction "3_3") (pintype "bidirectional"))
      (node (ref "J2") (pin "5") (pinfunction "5_5") (pintype "bidirectional"))
      (node (ref "J4") (pin "A12_B1") (pinfunction "GND_A12_B1") (pintype "power_in"))
      (node (ref "J4") (pin "A1_B12") (pinfunction "GND_A1_B12") (pintype "power_in"))
      (node (ref "J4") (pin "SH1") (pinfunction "SHIELD_SH1") (pintype "passive"))
      (node (ref "J4") (pin "SH2") (pinfunction "SHIELD_SH2") (pintype "passive"))
      (node (ref "J4") (pin "SH3") (pinfunction "SHIELD_SH3") (pintype "passive"))
      (node (ref "J4") (pin "SH4") (pinfunction "SHIELD_SH4") (pintype "passive"))
      (node (ref "R1_USB") (pin "1") (pinfunction "1_1") (pintype "bidirectional"))
      (node (ref "R2_EP_DR") (pin "1") (pinfunction "1_1") (pintype "bidirectional"))
      (node (ref "R2_USB") (pin "2") (pinfunction "2_2") (pintype "bidirectional"))
      (node (ref "R3") (pin "1") (pinfunction "1_1") (pintype "bidirectional"))
      (node (ref "R9") (pin "1") (pinfunction "1_1") (pintype "bidirectional"))
      (node (ref "R_TYPE_SEL") (pin "1") (pinfunction "1_1") (pintype "bidirectional"))
      (node (ref "SJ1") (pin "1") (pinfunction "1_1") (pintype "passive"))
      (node (ref "SW_DN") (pin "1") (pinfunction "1_1") (pintype "passive"))
      (node (ref "SW_ENT") (pin "1") (pinfunction "1_1") (pintype "passive"))
      (node (ref "SW_UP") (pin "1") (pinfunction "1_1") (pintype "passive"))
      (node (ref "TP_BAT_GND") (pin "TP") (pinfunction "TP_TP") (pintype "input"))
      (node (ref "TP_GND") (pin "TP") (pinfunction "TP_TP") (pintype "input"))
      (node (ref "U1") (pin "P$74") (pinfunction "VSS_PAD_P$74") (pintype "bidirectional"))
      (node (ref "U1") (pin "P$75") (pinfunction "VSS_PAD_P$75") (pintype "bidirectional"))
      (node (ref "U1") (pin "P$76") (pinfunction "VSS_PAD_P$76") (pintype "bidirectional"))
      (node (ref "U1") (pin "P$77") (pinfunction "VSS_PAD_P$77") (pintype "bidirectional"))
      (node (ref "U1") (pin "P$78") (pinfunction "VSS_PAD_P$78") (pintype "bidirectional"))
      (node (ref "U1") (pin "P$79") (pinfunction "VSS_PAD_P$79") (pintype "bidirectional"))
      (node (ref "U1") (pin "P$80") (pinfunction "VSS_PAD_P$80") (pintype "bidirectional"))
      (node (ref "U1") (pin "P$81") (pinfunction "VSS_PAD_P$81") (pintype "bidirectional"))
      (node (ref "U1") (pin "P$82") (pinfunction "VSS_PAD_P$82") (pintype "bidirectional"))
      (node (ref "U1") (pin "P$83") (pinfunction "VSS_PAD_P$83") (pintype "bidirectional"))
      (node (ref "U1") (pin "P$84") (pinfunction "VSS_PAD_P$84") (pintype "bidirectional"))
      (node (ref "U1") (pin "P$85") (pinfunction "VSS_PAD_P$85") (pintype "bidirectional"))
      (node (ref "U1") (pin "P$86") (pinfunction "VSS_PAD_P$86") (pintype "bidirectional"))
      (node (ref "U1") (pin "P$87") (pinfunction "VSS_PAD_P$87") (pintype "bidirectional"))
      (node (ref "U1") (pin "P$88") (pinfunction "VSS_PAD_P$88") (pintype "bidirectional"))
      (node (ref "U1") (pin "P$89") (pinfunction "VSS_PAD_P$89") (pintype "bidirectional"))
      (node (ref "U1") (pin "P$90") (pinfunction "VSS_PAD_P$90") (pintype "bidirectional"))
      (node (ref "U1") (pin "P$B7") (pinfunction "VSS_P$B7") (pintype "power_in"))
      (node (ref "U1") (pin "P$F23") (pinfunction "VSS_PA_P$F23") (pintype "bidirectional"))
      (node (ref "U3") (pin "1") (pinfunction "CTG_1") (pintype "power_in"))
      (node (ref "U3") (pin "4") (pinfunction "GND_4") (pintype "power_in"))
      (node (ref "U3") (pin "6") (pinfunction "QSTRT_6") (pintype "input"))
      (node (ref "U3") (pin "9") (pinfunction "EP_9") (pintype "power_in"))
      (node (ref "X1") (pin "2") (pinfunction "2_2") (pintype "passive"))
      (node (ref "X1") (pin "4") (pinfunction "4_4") (pintype "passive"))
    )
    (net (code "17") (name "HAPTIC_EN") (class "Default")
      (node (ref "IC2") (pin "A1") (pinfunction "EN_A1") (pintype "bidirectional"))
      (node (ref "U1") (pin "P$U1") (pinfunction "P0.12_P$U1") (pintype "bidirectional"))
    )
    (net (code "18") (name "IMU_INT1") (class "Default")
      (node (ref "IC3") (pin "5") (pinfunction "INT1_5") (pintype "bidirectional"))
      (node (ref "U1") (pin "P$N1") (pinfunction "P0.08_P$N1") (pintype "bidirectional"))
    )
    (net (code "19") (name "IMU_INT2") (class "Default")
      (node (ref "IC3") (pin "6") (pinfunction "INT2_6") (pintype "bidirectional"))
      (node (ref "U1") (pin "P$P2") (pinfunction "P1.08_P$P2") (pintype "bidirectional"))
    )
    (net (code "20") (name "LX1") (class "Default")
      (node (ref "IC9") (pin "B2") (pinfunction "SW1_1_B2") (pintype "bidirectional"))
      (node (ref "IC9") (pin "B3") (pinfunction "SW1_2_B3") (pintype "bidirectional"))
      (node (ref "L7") (pin "1") (pinfunction "1_1") (pintype "bidirectional"))
    )
    (net (code "21") (name "LX2") (class "Default")
      (node (ref "IC9") (pin "D2") (pinfunction "SW2_1_D2") (pintype "bidirectional"))
      (node (ref "IC9") (pin "D3") (pinfunction "SW2_2_D3") (pintype "bidirectional"))
      (node (ref "L7") (pin "2") (pinfunction "2_2") (pintype "bidirectional"))
    )
    (net (code "22") (name "MOSI") (class "Default")
      (node (ref "J1") (pin "14") (pinfunction "14_14") (pintype "bidirectional"))
      (node (ref "U1") (pin "P$B13") (pinfunction "P0.03/AIN1_P$B13") (pintype "bidirectional"))
    )
    (net (code "23") (name "Net-(D2-K)") (class "Default")
      (node (ref "C2-EP-DR") (pin "1") (pinfunction "1_1") (pintype "passive"))
      (node (ref "D2") (pin "1") (pinfunction "K_1") (pintype "bidirectional"))
      (node (ref "D4") (pin "2") (pinfunction "A_2") (pintype "bidirectional"))
    )
    (net (code "24") (name "Net-(D5-A)") (class "Default")
      (node (ref "C2-EP-DR") (pin "2") (pinfunction "2_2") (pintype "passive"))
      (node (ref "D5") (pin "2") (pinfunction "A_2") (pintype "bidirectional"))
      (node (ref "L5") (pin "1") (pinfunction "1_1") (pintype "passive"))
      (node (ref "Q3") (pin "3") (pinfunction "D_3") (pintype "bidirectional"))
    )
    (net (code "25") (name "Net-(EPD_C1-Pad2)") (class "Default")
      (node (ref "EPD_C1") (pin "2") (pinfunction "2_2") (pintype "passive"))
      (node (ref "J1") (pin "5") (pinfunction "5_5") (pintype "bidirectional"))
    )
    (net (code "26") (name "Net-(EPD_C2-Pad2)") (class "Default")
      (node (ref "EPD_C2") (pin "2") (pinfunction "2_2") (pintype "passive"))
      (node (ref "J1") (pin "4") (pinfunction "4_4") (pintype "bidirectional"))
    )
    (net (code "27") (name "Net-(EPD_C6-Pad2)") (class "Default")
      (node (ref "EPD_C6") (pin "2") (pinfunction "2_2") (pintype "passive"))
      (node (ref "J1") (pin "18") (pinfunction "18_18") (pintype "bidirectional"))
    )
    (net (code "28") (name "Net-(EPD_C7-Pad2)") (class "Default")
      (node (ref "EPD_C7") (pin "2") (pinfunction "2_2") (pintype "passive"))
      (node (ref "J1") (pin "19") (pinfunction "19_19") (pintype "bidirectional"))
    )
    (net (code "29") (name "Net-(EPD_C8-Pad2)") (class "Default")
      (node (ref "EPD_C8") (pin "2") (pinfunction "2_2") (pintype "passive"))
      (node (ref "J1") (pin "20") (pinfunction "20_20") (pintype "bidirectional"))
    )
    (net (code "30") (name "Net-(EPD_C10-Pad2)") (class "Default")
      (node (ref "EPD_C10") (pin "2") (pinfunction "2_2") (pintype "passive"))
      (node (ref "J1") (pin "22") (pinfunction "22_22") (pintype "bidirectional"))
    )
    (net (code "31") (name "Net-(EPD_C12-Pad2)") (class "Default")
      (node (ref "EPD_C12") (pin "2") (pinfunction "2_2") (pintype "passive"))
      (node (ref "J1") (pin "24") (pinfunction "24_24") (pintype "bidirectional"))
    )
    (net (code "32") (name "Net-(IC1-TS{slash}MR)") (class "Default")
      (node (ref "IC1") (pin "D1") (pinfunction "TS/MR_D1") (pintype "bidirectional"))
      (node (ref "R9") (pin "2") (pinfunction "2_2") (pintype "bidirectional"))
    )
    (net (code "33") (name "Net-(IC2-REG)") (class "Default")
      (node (ref "C32") (pin "2") (pinfunction "2_2") (pintype "passive"))
      (node (ref "IC2") (pin "A2") (pinfunction "REG_A2") (pintype "bidirectional"))
    )
    (net (code "34") (name "Net-(IC3-SDO)") (class "Default")
      (node (ref "IC3") (pin "1") (pinfunction "SDO_1") (pintype "bidirectional"))
      (node (ref "R3") (pin "2") (pinfunction "2_2") (pintype "bidirectional"))
    )
    (net (code "35") (name "Net-(IC9-SCL)") (class "Default")
      (node (ref "IC9") (pin "D1") (pinfunction "SCL_D1") (pintype "bidirectional"))
      (node (ref "R4") (pin "2") (pinfunction "2_2") (pintype "bidirectional"))
    )
    (net (code "36") (name "Net-(IC9-SDA)") (class "Default")
      (node (ref "IC9") (pin "E1") (pinfunction "SDA_E1") (pintype "bidirectional"))
      (node (ref "R2") (pin "2") (pinfunction "2_2") (pintype "bidirectional"))
    )
    (net (code "37") (name "Net-(J4-CC1)") (class "Default")
      (node (ref "J4") (pin "A5") (pinfunction "CC1_A5") (pintype "bidirectional"))
      (node (ref "R1_USB") (pin "2") (pinfunction "2_2") (pintype "bidirectional"))
    )
    (net (code "38") (name "Net-(J4-CC2)") (class "Default")
      (node (ref "J4") (pin "B5") (pinfunction "CC2_B5") (pintype "bidirectional"))
      (node (ref "R2_USB") (pin "1") (pinfunction "1_1") (pintype "bidirectional"))
    )
    (net (code "39") (name "Net-(L2-Pad2)") (class "Default")
      (node (ref "L2") (pin "2") (pinfunction "2_2") (pintype "passive"))
      (node (ref "L3") (pin "1") (pinfunction "1_1") (pintype "passive"))
    )
    (net (code "40") (name "Net-(R1_EP_DR-Pad1)") (class "Default")
      (node (ref "R1_EP_DR") (pin "1") (pinfunction "1_1") (pintype "bidirectional"))
      (node (ref "R_TYPE_SEL") (pin "2") (pinfunction "2_2") (pintype "bidirectional"))
      (node (ref "SJ1") (pin "2") (pinfunction "2_2") (pintype "passive"))
    )
    (net (code "41") (name "Net-(U1-ANT)") (class "Default")
      (node (ref "C3") (pin "1") (pinfunction "1_1") (pintype "passive"))
      (node (ref "L1") (pin "1") (pinfunction "1_1") (pintype "passive"))
      (node (ref "U1") (pin "P$H23") (pinfunction "ANT_P$H23") (pintype "bidirectional"))
    )
    (net (code "42") (name "Net-(U1-DCC)") (class "Default")
      (node (ref "L2") (pin "1") (pinfunction "1_1") (pintype "passive"))
      (node (ref "U1") (pin "P$B3") (pinfunction "DCC_P$B3") (pintype "output"))
    )
    (net (code "43") (name "Net-(U1-DEC2)") (class "Default")
      (node (ref "C13") (pin "1") (pinfunction "1_1") (pintype "passive"))
      (node (ref "U1") (pin "P$A18") (pinfunction "DEC2_P$A18") (pintype "bidirectional"))
    )
    (net (code "44") (name "Net-(U1-DEC3V3)") (class "Default")
      (node (ref "C20") (pin "1") (pinfunction "1_1") (pintype "passive"))
      (node (ref "U1") (pin "P$AC5") (pinfunction "DEC3V3_P$AC5") (pintype "bidirectional"))
    )
    (net (code "45") (name "Net-(U1-DEC5)") (class "Default")
      (node (ref "C9") (pin "1") (pinfunction "1_1") (pintype "passive"))
      (node (ref "U1") (pin "P$N24") (pinfunction "DEC5_P$N24") (pintype "bidirectional"))
    )
    (net (code "46") (name "Net-(U1-XC1)") (class "Default")
      (node (ref "C1") (pin "2") (pinfunction "2_2") (pintype "passive"))
      (node (ref "U1") (pin "P$B24") (pinfunction "XC1_P$B24") (pintype "input"))
      (node (ref "X1") (pin "1") (pinfunction "1_1") (pintype "passive"))
    )
    (net (code "47") (name "Net-(U1-XC2)") (class "Default")
      (node (ref "C2") (pin "2") (pinfunction "2_2") (pintype "passive"))
      (node (ref "U1") (pin "P$A23") (pinfunction "XC2_P$A23") (pintype "output"))
      (node (ref "X1") (pin "3") (pinfunction "3_3") (pintype "passive"))
    )
    (net (code "48") (name "OUT+") (class "Default")
      (node (ref "IC2") (pin "A3") (pinfunction "OUT+_A3") (pintype "bidirectional"))
      (node (ref "TP_OP") (pin "TP") (pinfunction "TP_TP") (pintype "input"))
    )
    (net (code "49") (name "OUT-") (class "Default")
      (node (ref "IC2") (pin "C3") (pinfunction "OUT-_C3") (pintype "bidirectional"))
      (node (ref "TP_ON") (pin "TP") (pinfunction "TP_TP") (pintype "input"))
    )
    (net (code "50") (name "P0.0{slash}XL1") (class "Default")
      (node (ref "C17") (pin "2") (pinfunction "2_2") (pintype "passive"))
      (node (ref "U1") (pin "P$D2") (pinfunction "P0.00/XL1_P$D2") (pintype "bidirectional"))
      (node (ref "X2") (pin "1") (pinfunction "1_1") (pintype "passive"))
    )
    (net (code "51") (name "P0.0{slash}XL2") (class "Default")
      (node (ref "C18") (pin "2") (pinfunction "2_2") (pintype "passive"))
      (node (ref "U1") (pin "P$F2") (pinfunction "P0.01/XL2_P$F2") (pintype "bidirectional"))
      (node (ref "X2") (pin "2") (pinfunction "2_2") (pintype "passive"))
    )
    (net (code "52") (name "P0.04") (class "Default")
      (node (ref "U1") (pin "P$J1") (pinfunction "P0.04/AIN2_P$J1") (pintype "bidirectional"))
    )
    (net (code "53") (name "P0.09") (class "Default")
      (node (ref "U1") (pin "P$L24") (pinfunction "P0.09/NFC1_P$L24") (pintype "bidirectional"))
    )
    (net (code "54") (name "P0.13") (class "Default")
      (node (ref "C30") (pin "2") (pinfunction "2_2") (pintype "passive"))
      (node (ref "R5") (pin "1") (pinfunction "1_1") (pintype "bidirectional"))
      (node (ref "SW_UP") (pin "2") (pinfunction "2_2") (pintype "passive"))
      (node (ref "U1") (pin "P$AD8") (pinfunction "P0.13_P$AD8") (pintype "bidirectional"))
    )
    (net (code "55") (name "P0.14") (class "Default")
      (node (ref "C31") (pin "2") (pinfunction "2_2") (pintype "passive"))
      (node (ref "R8") (pin "1") (pinfunction "1_1") (pintype "bidirectional"))
      (node (ref "SW_ENT") (pin "2") (pinfunction "2_2") (pintype "passive"))
      (node (ref "U1") (pin "P$AC9") (pinfunction "P0.14_P$AC9") (pintype "bidirectional"))
    )
    (net (code "56") (name "P0.19") (class "Default")
      (node (ref "U1") (pin "P$AC15") (pinfunction "P0.19_P$AC15") (pintype "bidirectional"))
    )
    (net (code "57") (name "P0.20") (class "Default")
      (node (ref "U1") (pin "P$AD16") (pinfunction "P0.20_P$AD16") (pintype "bidirectional"))
    )
    (net (code "58") (name "P0.21") (class "Default")
      (node (ref "U1") (pin "P$AC17") (pinfunction "P0.21_P$AC17") (pintype "bidirectional"))
    )
    (net (code "59") (name "P0.22") (class "Default")
      (node (ref "U1") (pin "P$AD18") (pinfunction "P0.22_P$AD18") (pintype "bidirectional"))
    )
    (net (code "60") (name "P0.23") (class "Default")
      (node (ref "U1") (pin "P$AC19") (pinfunction "P0.23_P$AC19") (pintype "bidirectional"))
    )
    (net (code "61") (name "P0.24") (class "Default")
      (node (ref "U1") (pin "P$AD20") (pinfunction "P0.24_P$AD20") (pintype "bidirectional"))
    )
    (net (code "62") (name "P0.25") (class "Default")
      (node (ref "U1") (pin "P$AC21") (pinfunction "P0.25_P$AC21") (pintype "bidirectional"))
    )
    (net (code "63") (name "P0.26") (class "Default")
      (node (ref "U1") (pin "P$G1") (pinfunction "P0.26_P$G1") (pintype "bidirectional"))
    )
    (net (code "64") (name "P0.27") (class "Default")
      (node (ref "U1") (pin "P$H2") (pinfunction "P0.27_P$H2") (pintype "bidirectional"))
    )
    (net (code "65") (name "P0.28") (class "Default")
      (node (ref "U1") (pin "P$B11") (pinfunction "P0.28/AIN4_P$B11") (pintype "bidirectional"))
    )
    (net (code "66") (name "P0.29") (class "Default")
      (node (ref "U1") (pin "P$A10") (pinfunction "P0.29/AIN5_P$A10") (pintype "bidirectional"))
    )
    (net (code "67") (name "P0.30") (class "Default")
      (node (ref "U1") (pin "P$B9") (pinfunction "P0.30/AIN6_P$B9") (pintype "bidirectional"))
    )
    (net (code "68") (name "P0.31") (class "Default")
      (node (ref "U1") (pin "P$A8") (pinfunction "P0.31/AIN7_P$A8") (pintype "bidirectional"))
    )
    (net (code "69") (name "P1.01") (class "Default")
      (node (ref "Q1") (pin "1") (pinfunction "G_1") (pintype "bidirectional"))
      (node (ref "R_PWR_EPD") (pin "1") (pinfunction "1_1") (pintype "bidirectional"))
      (node (ref "U1") (pin "P$Y23") (pinfunction "P1.01_P$Y23") (pintype "bidirectional"))
    )
    (net (code "70") (name "P1.02") (class "Default")
      (node (ref "C29") (pin "2") (pinfunction "2_2") (pintype "passive"))
      (node (ref "R7") (pin "1") (pinfunction "1_1") (pintype "bidirectional"))
      (node (ref "SW_DN") (pin "2") (pinfunction "2_2") (pintype "passive"))
      (node (ref "U1") (pin "P$W24") (pinfunction "P1.02_P$W24") (pintype "bidirectional"))
    )
    (net (code "71") (name "P1.03") (class "Default")
      (node (ref "U1") (pin "P$V23") (pinfunction "P1.03_P$V23") (pintype "bidirectional"))
    )
    (net (code "72") (name "P1.04") (class "Default")
      (node (ref "U1") (pin "P$U24") (pinfunction "P1.04_P$U24") (pintype "bidirectional"))
    )
    (net (code "73") (name "P1.05") (class "Default")
      (node (ref "U1") (pin "P$T23") (pinfunction "P1.05_P$T23") (pintype "bidirectional"))
    )
    (net (code "74") (name "P1.06") (class "Default")
      (node (ref "U1") (pin "P$R24") (pinfunction "P1.06_P$R24") (pintype "bidirectional"))
    )
    (net (code "75") (name "P1.07") (class "Default")
      (node (ref "U1") (pin "P$P23") (pinfunction "P1.07_P$P23") (pintype "bidirectional"))
    )
    (net (code "76") (name "P1.09") (class "Default")
      (node (ref "U1") (pin "P$R1") (pinfunction "P1.09_P$R1") (pintype "bidirectional"))
    )
    (net (code "77") (name "P1.10") (class "Default")
      (node (ref "U1") (pin "P$A20") (pinfunction "P1.10_P$A20") (pintype "bidirectional"))
    )
    (net (code "78") (name "P1.11") (class "Default")
      (node (ref "U1") (pin "P$B19") (pinfunction "P1.11_P$B19") (pintype "bidirectional"))
    )
    (net (code "79") (name "P1.12") (class "Default")
      (node (ref "U1") (pin "P$B17") (pinfunction "P1.12_P$B17") (pintype "bidirectional"))
    )
    (net (code "80") (name "P1.13") (class "Default")
      (node (ref "U1") (pin "P$A16") (pinfunction "P1.13_P$A16") (pintype "bidirectional"))
    )
    (net (code "81") (name "P1.14") (class "Default")
      (node (ref "U1") (pin "P$B15") (pinfunction "P1.14_P$B15") (pintype "bidirectional"))
    )
    (net (code "82") (name "P1.15") (class "Default")
      (node (ref "U1") (pin "P$A14") (pinfunction "P1.15_P$A14") (pintype "bidirectional"))
    )
    (net (code "83") (name "PMIC_INT") (class "Default")
      (node (ref "IC1") (pin "A1") (pinfunction "~{INT}_A1") (pintype "bidirectional"))
      (node (ref "U1") (pin "P$T2") (pinfunction "P0.11_P$T2") (pintype "bidirectional"))
    )
    (net (code "84") (name "PREVGH") (class "Default")
      (node (ref "D5") (pin "1") (pinfunction "K_1") (pintype "bidirectional"))
      (node (ref "EPD_C9") (pin "2") (pinfunction "2_2") (pintype "passive"))
      (node (ref "J1") (pin "21") (pinfunction "21_21") (pintype "bidirectional"))
    )
    (net (code "85") (name "PREVGL") (class "Default")
      (node (ref "D2") (pin "2") (pinfunction "A_2") (pintype "bidirectional"))
      (node (ref "EPD_C11") (pin "2") (pinfunction "2_2") (pintype "passive"))
      (node (ref "J1") (pin "23") (pinfunction "23_23") (pintype "bidirectional"))
    )
    (net (code "86") (name "RESET") (class "Default")
      (node (ref "J1") (pin "3") (pinfunction "3_3") (pintype "bidirectional"))
      (node (ref "J2") (pin "6") (pinfunction "6_6") (pintype "bidirectional"))
      (node (ref "Q3") (pin "2") (pinfunction "S_2") (pintype "bidirectional"))
      (node (ref "R1_EP_DR") (pin "2") (pinfunction "2_2") (pintype "bidirectional"))
      (node (ref "TP_RESET") (pin "TP") (pinfunction "TP_TP") (pintype "input"))
      (node (ref "U1") (pin "P$AC13") (pinfunction "P0.18/RESET_P$AC13") (pintype "bidirectional"))
    )
    (net (code "87") (name "RF") (class "Default")
      (node (ref "ANT1") (pin "1") (pinfunction "FEED_1") (pintype "input"))
      (node (ref "C22") (pin "1") (pinfunction "1_1") (pintype "passive"))
      (node (ref "C4") (pin "1") (pinfunction "1_1") (pintype "passive"))
      (node (ref "L1") (pin "2") (pinfunction "2_2") (pintype "passive"))
    )
    (net (code "88") (name "SCK") (class "Default")
      (node (ref "J1") (pin "13") (pinfunction "13_13") (pintype "bidirectional"))
      (node (ref "U1") (pin "P$A12") (pinfunction "P0.02/AIN0_P$A12") (pintype "bidirectional"))
    )
    (net (code "89") (name "SCL") (class "Default")
      (node (ref "IC1") (pin "B1") (pinfunction "SCL_B1") (pintype "bidirectional"))
      (node (ref "IC2") (pin "C1") (pinfunction "SCL_C1") (pintype "bidirectional"))
      (node (ref "IC3") (pin "12") (pinfunction "SCX_12") (pintype "bidirectional"))
      (node (ref "R17") (pin "2") (pinfunction "2_2") (pintype "bidirectional"))
      (node (ref "R4") (pin "1") (pinfunction "1_1") (pintype "bidirectional"))
      (node (ref "TP_SCL") (pin "TP") (pinfunction "TP_TP") (pintype "input"))
      (node (ref "U1") (pin "P$M2") (pinfunction "P0.07_P$M2") (pintype "bidirectional"))
      (node (ref "U3") (pin "7") (pinfunction "SCL_7") (pintype "input"))
    )
    (net (code "90") (name "SDA") (class "Default")
      (node (ref "IC1") (pin "C1") (pinfunction "SDA_C1") (pintype "bidirectional"))
      (node (ref "IC2") (pin "B2") (pinfunction "SDA_B2") (pintype "bidirectional"))
      (node (ref "IC3") (pin "2") (pinfunction "SDX_2") (pintype "bidirectional"))
      (node (ref "R18") (pin "2") (pinfunction "2_2") (pintype "bidirectional"))
      (node (ref "R2") (pin "1") (pinfunction "1_1") (pintype "bidirectional"))
      (node (ref "TP_SDA") (pin "TP") (pinfunction "TP_TP") (pintype "input"))
      (node (ref "U1") (pin "P$L1") (pinfunction "P0.06_P$L1") (pintype "bidirectional"))
      (node (ref "U3") (pin "8") (pinfunction "SDA_8") (pintype "bidirectional"))
    )
    (net (code "91") (name "SWDCLK") (class "Default")
      (node (ref "J2") (pin "4") (pinfunction "4_4") (pintype "bidirectional"))
      (node (ref "TP_SWDCLK") (pin "TP") (pinfunction "TP_TP") (pintype "input"))
      (node (ref "U1") (pin "P$AA24") (pinfunction "SWDCLK_P$AA24") (pintype "input"))
    )
    (net (code "92") (name "SWDIO") (class "Default")
      (node (ref "J2") (pin "2") (pinfunction "2_2") (pintype "bidirectional"))
      (node (ref "TP_SWDIO") (pin "TP") (pinfunction "TP_TP") (pintype "input"))
      (node (ref "U1") (pin "P$AC24") (pinfunction "SWDIO_P$AC24") (pintype "bidirectional"))
    )
    (net (code "93") (name "SWO") (class "Default")
      (node (ref "TP_SWO") (pin "TP") (pinfunction "TP_TP") (pintype "input"))
      (node (ref "U1") (pin "P$AD22") (pinfunction "P1.00_P$AD22") (pintype "bidirectional"))
    )
    (net (code "94") (name "VBAT") (class "Default")
      (node (ref "C27") (pin "2") (pinfunction "2_2") (pintype "passive"))
      (node (ref "C37") (pin "2") (pinfunction "2_2") (pintype "passive"))
      (node (ref "IC1") (pin "C2") (pinfunction "BAT_C2") (pintype "bidirectional"))
      (node (ref "TP_VBAT") (pin "TP") (pinfunction "TP_TP") (pintype "input"))
      (node (ref "U3") (pin "2") (pinfunction "CELL_2") (pintype "power_in"))
      (node (ref "U3") (pin "3") (pinfunction "VDD_3") (pintype "power_in"))
    )
    (net (code "95") (name "VBUS") (class "Default")
      (node (ref "C21") (pin "1") (pinfunction "1_1") (pintype "passive"))
      (node (ref "C38") (pin "2") (pinfunction "2_2") (pintype "passive"))
      (node (ref "C42") (pin "1") (pinfunction "1_1") (pintype "passive"))
      (node (ref "C43") (pin "2") (pinfunction "2_2") (pintype "passive"))
      (node (ref "D3") (pin "5") (pinfunction "VBUS_5") (pintype "bidirectional"))
      (node (ref "IC1") (pin "A2") (pinfunction "IN_A2") (pintype "bidirectional"))
      (node (ref "J4") (pin "A4_B9") (pinfunction "VBUS_A4_B9") (pintype "power_in"))
      (node (ref "J4") (pin "A9_B4") (pinfunction "VBUS_A9_B4") (pintype "power_in"))
      (node (ref "U1") (pin "P$AD2") (pinfunction "VBUS_P$AD2") (pintype "power_in"))
    )
    (net (code "96") (name "VREG") (class "Default")
      (node (ref "C23") (pin "2") (pinfunction "2_2") (pintype "passive"))
      (node (ref "C24") (pin "2") (pinfunction "2_2") (pintype "passive"))
      (node (ref "C39") (pin "1") (pinfunction "1_1") (pintype "passive"))
      (node (ref "IC1") (pin "B2") (pinfunction "SYS_B2") (pintype "bidirectional"))
      (node (ref "IC9") (pin "A1") (pinfunction "EN_A1") (pintype "bidirectional"))
      (node (ref "IC9") (pin "A2") (pinfunction "VIN_1_A2") (pintype "bidirectional"))
      (node (ref "IC9") (pin "A3") (pinfunction "VIN_2_A3") (pintype "bidirectional"))
      (node (ref "TP_VREG") (pin "TP") (pinfunction "TP_TP") (pintype "input"))
    )
    (net (code "97") (name "unconnected-(ANT1-NC-Pad2)") (class "Default")
      (node (ref "ANT1") (pin "2") (pinfunction "NC_2") (pintype "no_connect"))
    )
    (net (code "98") (name "unconnected-(IC3-ASCL-Pad11)") (class "Default")
      (node (ref "IC3") (pin "11") (pinfunction "ASCL_11") (pintype "bidirectional"))
    )
    (net (code "99") (name "unconnected-(IC3-ASDA-Pad4)") (class "Default")
      (node (ref "IC3") (pin "4") (pinfunction "ASDA_4") (pintype "bidirectional"))
    )
    (net (code "100") (name "unconnected-(J1-Pad1)") (class "Default")
      (node (ref "J1") (pin "1") (pinfunction "1_1") (pintype "bidirectional"))
    )
    (net (code "101") (name "unconnected-(J1-Pad6)") (class "Default")
      (node (ref "J1") (pin "6") (pinfunction "6_6") (pintype "bidirectional"))
    )
    (net (code "102") (name "unconnected-(J1-Pad7)") (class "Default")
      (node (ref "J1") (pin "7") (pinfunction "7_7") (pintype "bidirectional"))
    )
    (net (code "103") (name "unconnected-(J4-SBU1-PadA8)") (class "Default")
      (node (ref "J4") (pin "A8") (pinfunction "SBU1_A8") (pintype "bidirectional"))
    )
    (net (code "104") (name "unconnected-(J4-SBU2-PadB8)") (class "Default")
      (node (ref "J4") (pin "B8") (pinfunction "SBU2_B8") (pintype "bidirectional"))
    )
    (net (code "105") (name "unconnected-(U1-DCCH-PadP$AB2)") (class "Default")
      (node (ref "U1") (pin "P$AB2") (pinfunction "DCCH_P$AB2") (pintype "bidirectional"))
    )
  )
)
